# InexpensiveTNC-v4-mod.net
KiCad netlist of a schematic drawn in EAGLE
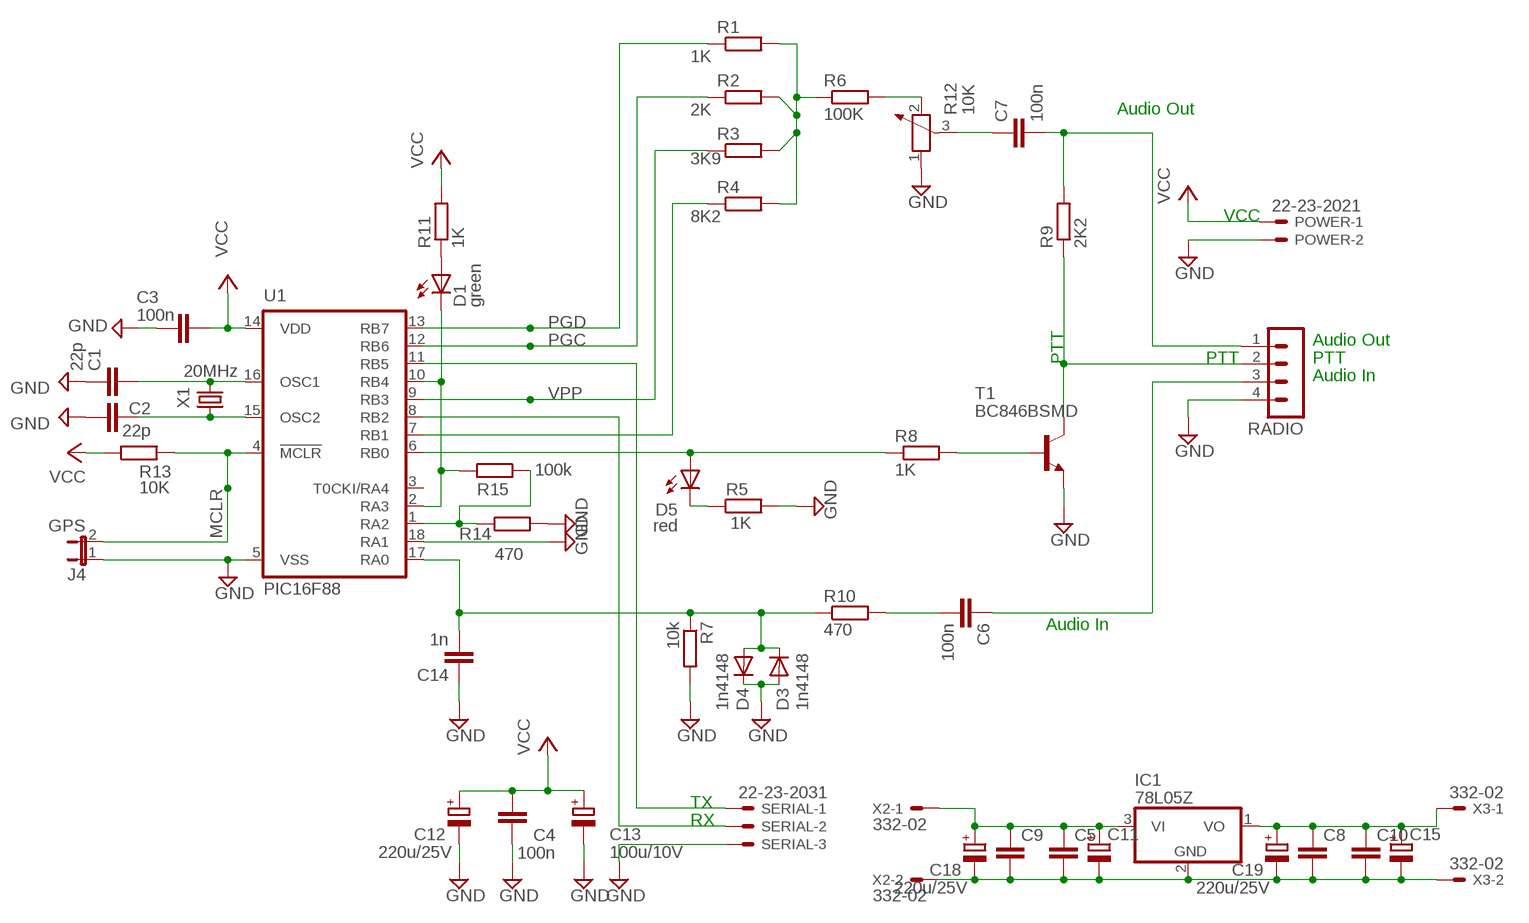
[diagram p0: schematic, sheet 1]

(export (version "E")
  (design (tool "Eeschema 10.0.6"))
  (components
    (comp (ref "C1")
      (value "22p")
      (footprint "eagle-import:C0805")
      (libsource (lib "eagle-import") (part "C-EUC0805"))
    )
    (comp (ref "C2")
      (value "22p")
      (footprint "eagle-import:C0805")
      (libsource (lib "eagle-import") (part "C-EUC0805"))
    )
    (comp (ref "C3")
      (value "100n")
      (footprint "eagle-import:C0805")
      (libsource (lib "eagle-import") (part "C-EUC0805"))
    )
    (comp (ref "C4")
      (value "100n")
      (footprint "eagle-import:C0805")
      (libsource (lib "eagle-import") (part "C-EUC0805"))
    )
    (comp (ref "C5")
      (value "C-EU025-025X050")
      (footprint "eagle-import:C025-025X050")
      (libsource (lib "eagle-import") (part "C-EU025-025X050"))
    )
    (comp (ref "C6")
      (value "100n")
      (footprint "eagle-import:C0805")
      (libsource (lib "eagle-import") (part "C-EUC0805"))
    )
    (comp (ref "C7")
      (value "100n")
      (footprint "eagle-import:C0805")
      (libsource (lib "eagle-import") (part "C-EUC0805"))
    )
    (comp (ref "C8")
      (value "C-EU025-025X050")
      (footprint "eagle-import:C025-025X050")
      (libsource (lib "eagle-import") (part "C-EU025-025X050"))
    )
    (comp (ref "C9")
      (value "C-EUC0805K")
      (footprint "eagle-import:C0805K")
      (libsource (lib "eagle-import") (part "C-EUC0805K"))
    )
    (comp (ref "C10")
      (value "C-EUC0805K")
      (footprint "eagle-import:C0805K")
      (libsource (lib "eagle-import") (part "C-EUC0805K"))
    )
    (comp (ref "C11")
      (value "CPOL-EUE3.5-10")
      (footprint "eagle-import:E3,5-10")
      (libsource (lib "eagle-import") (part "CPOL-EUE3.5-10"))
    )
    (comp (ref "C12")
      (value "220u/25V")
      (footprint "eagle-import:PANASONIC_A")
      (libsource (lib "eagle-import") (part "CPOL-EUA"))
    )
    (comp (ref "C13")
      (value "100u/10V")
      (footprint "eagle-import:PANASONIC_A")
      (libsource (lib "eagle-import") (part "CPOL-EUA"))
    )
    (comp (ref "C14")
      (value "1n")
      (footprint "eagle-import:C0805")
      (libsource (lib "eagle-import") (part "C-EUC0805"))
    )
    (comp (ref "C15")
      (value "CPOL-EUE3.5-10")
      (footprint "eagle-import:E3,5-10")
      (libsource (lib "eagle-import") (part "CPOL-EUE3.5-10"))
    )
    (comp (ref "C18")
      (value "220u/25V")
      (footprint "eagle-import:PANASONIC_A")
      (libsource (lib "eagle-import") (part "CPOL-EUA"))
    )
    (comp (ref "C19")
      (value "220u/25V")
      (footprint "eagle-import:PANASONIC_A")
      (libsource (lib "eagle-import") (part "CPOL-EUA"))
    )
    (comp (ref "D1")
      (value "green")
      (footprint "eagle-import:CHIPLED_1206")
      (libsource (lib "eagle-import") (part "LEDCHIPLED_1206"))
    )
    (comp (ref "D3")
      (value "1n4148")
      (footprint "eagle-import:MINIMELF")
      (libsource (lib "eagle-import") (part "DIODE-MINIMELF"))
    )
    (comp (ref "D4")
      (value "1n4148")
      (footprint "eagle-import:MINIMELF")
      (libsource (lib "eagle-import") (part "DIODE-MINIMELF"))
    )
    (comp (ref "D5")
      (value "red")
      (footprint "eagle-import:CHIPLED_1206")
      (libsource (lib "eagle-import") (part "LEDCHIPLED_1206"))
    )
    (comp (ref "IC1")
      (value "78L05Z")
      (footprint "eagle-import:TO92")
      (libsource (lib "eagle-import") (part "78ZL05"))
    )
    (comp (ref "J4")
      (value "GPS")
      (footprint "eagle-import:JP1")
      (libsource (lib "eagle-import") (part "JP1E"))
    )
    (comp (ref "POWER")
      (value "22-23-2021")
      (footprint "eagle-import:22-23-2021")
      (fields (field (name "MF") "MOLEX"))
      (libsource (lib "eagle-import") (part "22-23-2021"))
    )
    (comp (ref "R1")
      (value "1K")
      (footprint "eagle-import:R0805W")
      (libsource (lib "eagle-import") (part "R-EU_R0805W"))
    )
    (comp (ref "R2")
      (value "2K")
      (footprint "eagle-import:R0805W")
      (libsource (lib "eagle-import") (part "R-EU_R0805W"))
    )
    (comp (ref "R3")
      (value "3K9")
      (footprint "eagle-import:R0805W")
      (libsource (lib "eagle-import") (part "R-EU_R0805W"))
    )
    (comp (ref "R4")
      (value "8K2")
      (footprint "eagle-import:R0805W")
      (libsource (lib "eagle-import") (part "R-EU_R0805W"))
    )
    (comp (ref "R5")
      (value "1K")
      (footprint "eagle-import:R0805W")
      (libsource (lib "eagle-import") (part "R-EU_R0805W"))
    )
    (comp (ref "R6")
      (value "100K")
      (footprint "eagle-import:R0805W")
      (libsource (lib "eagle-import") (part "R-EU_R0805W"))
    )
    (comp (ref "R7")
      (value "10k")
      (footprint "eagle-import:R0805W")
      (libsource (lib "eagle-import") (part "R-EU_R0805W"))
    )
    (comp (ref "R8")
      (value "1K")
      (footprint "eagle-import:R0805W")
      (libsource (lib "eagle-import") (part "R-EU_R0805W"))
    )
    (comp (ref "R9")
      (value "2K2")
      (footprint "eagle-import:R0805W")
      (libsource (lib "eagle-import") (part "R-EU_R0805W"))
    )
    (comp (ref "R10")
      (value "470")
      (footprint "eagle-import:R0805W")
      (libsource (lib "eagle-import") (part "R-EU_R0805W"))
    )
    (comp (ref "R11")
      (value "1K")
      (footprint "eagle-import:R0805W")
      (libsource (lib "eagle-import") (part "R-EU_R0805W"))
    )
    (comp (ref "R12")
      (value "10K")
      (footprint "eagle-import:PT-10S")
      (libsource (lib "eagle-import") (part "POTENTIOMETER_PT-10S"))
    )
    (comp (ref "R13")
      (value "10K")
      (footprint "eagle-import:R0805W")
      (libsource (lib "eagle-import") (part "R-EU_R0805W"))
    )
    (comp (ref "R14")
      (value "470")
      (footprint "eagle-import:R0805W")
      (libsource (lib "eagle-import") (part "R-EU_R0805W"))
    )
    (comp (ref "R15")
      (value "100k")
      (footprint "eagle-import:R0805W")
      (libsource (lib "eagle-import") (part "R-EU_R0805W"))
    )
    (comp (ref "RADIO")
      (value "MA04-1")
      (footprint "eagle-import:MA04-1")
      (libsource (lib "eagle-import") (part "MA04-1"))
    )
    (comp (ref "SERIAL")
      (value "22-23-2031")
      (footprint "eagle-import:22-23-2031")
      (fields (field (name "MF") "MOLEX"))
      (libsource (lib "eagle-import") (part "22-23-2031"))
    )
    (comp (ref "T1")
      (value "BC846BSMD")
      (footprint "eagle-import:SOT23")
      (libsource (lib "eagle-import") (part "BC846SMDB"))
    )
    (comp (ref "U1")
      (value "PIC16F88")
      (footprint "eagle-import:SO-18W")
      (fields
        (field (name "MF") "MICROCHIP")
        (field (name "MPN") "PIC16F83-04/SO")
        (field (name "MPN_1") "PIC16F83-04/SO")
        (field (name "OC_FARNELL") "unknown")
        (field (name "OC_NEWARK") "23C4997")
      )
      (libsource (lib "eagle-import") (part "PIC16F8SO3"))
    )
    (comp (ref "X1")
      (value "20MHz")
      (footprint "eagle-import:HC49U70")
      (libsource (lib "eagle-import") (part "CRYSTALHC49U70"))
    )
    (comp (ref "X2")
      (value "332-02")
      (footprint "eagle-import:332-02")
      (libsource (lib "eagle-import") (part "332-02"))
    )
    (comp (ref "X3")
      (value "332-02")
      (footprint "eagle-import:332-02")
      (libsource (lib "eagle-import") (part "332-02"))
    )
  )
  (nets
    (net (code "1") (name "/MCLR") (class "Default")
      (node (ref "J4") (pin "2") (pinfunction "2_2") (pintype "passive"))
      (node (ref "R13") (pin "2") (pinfunction "2_2") (pintype "passive"))
      (node (ref "U1") (pin "4") (pinfunction "~{MCLR}_4") (pintype "input"))
    )
    (net (code "2") (name "/PGC") (class "Default")
      (node (ref "R2") (pin "1") (pinfunction "1_1") (pintype "passive"))
      (node (ref "U1") (pin "12") (pinfunction "RB6_12") (pintype "bidirectional"))
    )
    (net (code "3") (name "/PGD") (class "Default")
      (node (ref "R1") (pin "1") (pinfunction "1_1") (pintype "passive"))
      (node (ref "U1") (pin "13") (pinfunction "RB7_13") (pintype "bidirectional"))
    )
    (net (code "4") (name "/VPP") (class "Default")
      (node (ref "R3") (pin "1") (pinfunction "1_1") (pintype "passive"))
      (node (ref "U1") (pin "9") (pinfunction "RB3_9") (pintype "bidirectional"))
    )
    (net (code "5") (name "GND") (class "Default")
      (node (ref "C1") (pin "1") (pinfunction "1_1") (pintype "passive"))
      (node (ref "C12") (pin "-") (pinfunction "-_-") (pintype "passive"))
      (node (ref "C13") (pin "-") (pinfunction "-_-") (pintype "passive"))
      (node (ref "C14") (pin "1") (pinfunction "1_1") (pintype "passive"))
      (node (ref "C2") (pin "1") (pinfunction "1_1") (pintype "passive"))
      (node (ref "C3") (pin "2") (pinfunction "2_2") (pintype "passive"))
      (node (ref "C4") (pin "1") (pinfunction "1_1") (pintype "passive"))
      (node (ref "D3") (pin "A") (pinfunction "A_A") (pintype "passive"))
      (node (ref "D4") (pin "C") (pinfunction "C_C") (pintype "passive"))
      (node (ref "J4") (pin "1") (pinfunction "1_1") (pintype "passive"))
      (node (ref "POWER") (pin "2") (pinfunction "S_2") (pintype "passive"))
      (node (ref "R12") (pin "1") (pinfunction "1_1") (pintype "passive"))
      (node (ref "R14") (pin "2") (pinfunction "2_2") (pintype "passive"))
      (node (ref "R5") (pin "2") (pinfunction "2_2") (pintype "passive"))
      (node (ref "R7") (pin "2") (pinfunction "2_2") (pintype "passive"))
      (node (ref "RADIO") (pin "4") (pinfunction "4_4") (pintype "passive"))
      (node (ref "SERIAL") (pin "3") (pinfunction "S_3") (pintype "passive"))
      (node (ref "T1") (pin "2") (pinfunction "E_2") (pintype "passive"))
      (node (ref "U1") (pin "18") (pinfunction "RA1_18") (pintype "bidirectional"))
      (node (ref "U1") (pin "5") (pinfunction "VSS_5") (pintype "power_in"))
    )
    (net (code "6") (name "Net-(C6-Pad1)") (class "Default")
      (node (ref "C6") (pin "1") (pinfunction "1_1") (pintype "passive"))
      (node (ref "RADIO") (pin "3") (pinfunction "3_3") (pintype "passive"))
    )
    (net (code "7") (name "Net-(C6-Pad2)") (class "Default")
      (node (ref "C6") (pin "2") (pinfunction "2_2") (pintype "passive"))
      (node (ref "R10") (pin "2") (pinfunction "2_2") (pintype "passive"))
    )
    (net (code "8") (name "Net-(C7-Pad1)") (class "Default")
      (node (ref "C7") (pin "1") (pinfunction "1_1") (pintype "passive"))
      (node (ref "R12") (pin "3") (pinfunction "3_3") (pintype "passive"))
    )
    (net (code "9") (name "Net-(C7-Pad2)") (class "Default")
      (node (ref "C7") (pin "2") (pinfunction "2_2") (pintype "passive"))
      (node (ref "R9") (pin "2") (pinfunction "2_2") (pintype "passive"))
      (node (ref "RADIO") (pin "1") (pinfunction "1_1") (pintype "passive"))
    )
    (net (code "10") (name "Net-(D1-PadA)") (class "Default")
      (node (ref "D1") (pin "A") (pinfunction "A_A") (pintype "passive"))
      (node (ref "R11") (pin "1") (pinfunction "1_1") (pintype "passive"))
    )
    (net (code "11") (name "Net-(D5-PadC)") (class "Default")
      (node (ref "D5") (pin "C") (pinfunction "C_C") (pintype "passive"))
      (node (ref "R5") (pin "1") (pinfunction "1_1") (pintype "passive"))
    )
    (net (code "12") (name "Net-(IC1-GND)") (class "Default")
      (node (ref "C10") (pin "2") (pinfunction "2_2") (pintype "passive"))
      (node (ref "C11") (pin "-") (pinfunction "-_-") (pintype "passive"))
      (node (ref "C15") (pin "-") (pinfunction "-_-") (pintype "passive"))
      (node (ref "C18") (pin "-") (pinfunction "-_-") (pintype "passive"))
      (node (ref "C19") (pin "-") (pinfunction "-_-") (pintype "passive"))
      (node (ref "C5") (pin "2") (pinfunction "2_2") (pintype "passive"))
      (node (ref "C8") (pin "2") (pinfunction "2_2") (pintype "passive"))
      (node (ref "C9") (pin "2") (pinfunction "2_2") (pintype "passive"))
      (node (ref "IC1") (pin "2") (pinfunction "GND_2") (pintype "passive"))
      (node (ref "X2") (pin "2") (pinfunction "S_2") (pintype "passive"))
      (node (ref "X3") (pin "2") (pinfunction "S_2") (pintype "passive"))
    )
    (net (code "13") (name "Net-(IC1-VI)") (class "Default")
      (node (ref "C11") (pin "+") (pinfunction "+_+") (pintype "passive"))
      (node (ref "C18") (pin "+") (pinfunction "+_+") (pintype "passive"))
      (node (ref "C5") (pin "1") (pinfunction "1_1") (pintype "passive"))
      (node (ref "C9") (pin "1") (pinfunction "1_1") (pintype "passive"))
      (node (ref "IC1") (pin "3") (pinfunction "VI_3") (pintype "input"))
      (node (ref "X2") (pin "1") (pinfunction "S_1") (pintype "passive"))
    )
    (net (code "14") (name "Net-(IC1-VO)") (class "Default")
      (node (ref "C10") (pin "1") (pinfunction "1_1") (pintype "passive"))
      (node (ref "C15") (pin "+") (pinfunction "+_+") (pintype "passive"))
      (node (ref "C19") (pin "+") (pinfunction "+_+") (pintype "passive"))
      (node (ref "C8") (pin "1") (pinfunction "1_1") (pintype "passive"))
      (node (ref "IC1") (pin "1") (pinfunction "VO_1") (pintype "passive"))
      (node (ref "X3") (pin "1") (pinfunction "S_1") (pintype "passive"))
    )
    (net (code "15") (name "Net-(R1-Pad2)") (class "Default")
      (node (ref "R1") (pin "2") (pinfunction "2_2") (pintype "passive"))
      (node (ref "R2") (pin "2") (pinfunction "2_2") (pintype "passive"))
      (node (ref "R3") (pin "2") (pinfunction "2_2") (pintype "passive"))
      (node (ref "R4") (pin "2") (pinfunction "2_2") (pintype "passive"))
      (node (ref "R6") (pin "1") (pinfunction "1_1") (pintype "passive"))
    )
    (net (code "16") (name "Net-(R12-Pad2)") (class "Default")
      (node (ref "R12") (pin "2") (pinfunction "2_2") (pintype "passive"))
      (node (ref "R6") (pin "2") (pinfunction "2_2") (pintype "passive"))
    )
    (net (code "17") (name "Net-(SERIALA-S)") (class "Default")
      (node (ref "SERIAL") (pin "1") (pinfunction "S_1") (pintype "passive"))
      (node (ref "U1") (pin "11") (pinfunction "RB5_11") (pintype "bidirectional"))
    )
    (net (code "18") (name "Net-(SERIALB-S)") (class "Default")
      (node (ref "SERIAL") (pin "2") (pinfunction "S_2") (pintype "passive"))
      (node (ref "U1") (pin "8") (pinfunction "RB2_8") (pintype "bidirectional"))
    )
    (net (code "19") (name "Net-(T1-B)") (class "Default")
      (node (ref "R8") (pin "2") (pinfunction "2_2") (pintype "passive"))
      (node (ref "T1") (pin "1") (pinfunction "B_1") (pintype "passive"))
    )
    (net (code "20") (name "Net-(T1-C)") (class "Default")
      (node (ref "R9") (pin "1") (pinfunction "1_1") (pintype "passive"))
      (node (ref "RADIO") (pin "2") (pinfunction "2_2") (pintype "passive"))
      (node (ref "T1") (pin "3") (pinfunction "C_3") (pintype "passive"))
    )
    (net (code "21") (name "Net-(U1-OSC1)") (class "Default")
      (node (ref "C1") (pin "2") (pinfunction "2_2") (pintype "passive"))
      (node (ref "U1") (pin "16") (pinfunction "OSC1_16") (pintype "input"))
      (node (ref "X1") (pin "2") (pinfunction "2_2") (pintype "passive"))
    )
    (net (code "22") (name "Net-(U1-OSC2)") (class "Default")
      (node (ref "C2") (pin "2") (pinfunction "2_2") (pintype "passive"))
      (node (ref "U1") (pin "15") (pinfunction "OSC2_15") (pintype "output"))
      (node (ref "X1") (pin "1") (pinfunction "1_1") (pintype "passive"))
    )
    (net (code "23") (name "Net-(U1-RA0)") (class "Default")
      (node (ref "C14") (pin "2") (pinfunction "2_2") (pintype "passive"))
      (node (ref "D3") (pin "C") (pinfunction "C_C") (pintype "passive"))
      (node (ref "D4") (pin "A") (pinfunction "A_A") (pintype "passive"))
      (node (ref "R10") (pin "1") (pinfunction "1_1") (pintype "passive"))
      (node (ref "R7") (pin "1") (pinfunction "1_1") (pintype "passive"))
      (node (ref "U1") (pin "17") (pinfunction "RA0_17") (pintype "bidirectional"))
    )
    (net (code "24") (name "Net-(U1-RA2)") (class "Default")
      (node (ref "R14") (pin "1") (pinfunction "1_1") (pintype "passive"))
      (node (ref "R15") (pin "1") (pinfunction "1_1") (pintype "passive"))
      (node (ref "U1") (pin "1") (pinfunction "RA2_1") (pintype "bidirectional"))
    )
    (net (code "25") (name "Net-(U1-RA3)") (class "Default")
      (node (ref "D1") (pin "C") (pinfunction "C_C") (pintype "passive"))
      (node (ref "R15") (pin "2") (pinfunction "2_2") (pintype "passive"))
      (node (ref "U1") (pin "10") (pinfunction "RB4_10") (pintype "bidirectional"))
      (node (ref "U1") (pin "2") (pinfunction "RA3_2") (pintype "bidirectional"))
    )
    (net (code "26") (name "Net-(U1-RB0)") (class "Default")
      (node (ref "D5") (pin "A") (pinfunction "A_A") (pintype "passive"))
      (node (ref "R8") (pin "1") (pinfunction "1_1") (pintype "passive"))
      (node (ref "U1") (pin "6") (pinfunction "RB0_6") (pintype "bidirectional"))
    )
    (net (code "27") (name "Net-(U1-RB1)") (class "Default")
      (node (ref "R4") (pin "1") (pinfunction "1_1") (pintype "passive"))
      (node (ref "U1") (pin "7") (pinfunction "RB1_7") (pintype "bidirectional"))
    )
    (net (code "28") (name "VCC") (class "Default")
      (node (ref "C12") (pin "+") (pinfunction "+_+") (pintype "passive"))
      (node (ref "C13") (pin "+") (pinfunction "+_+") (pintype "passive"))
      (node (ref "C3") (pin "1") (pinfunction "1_1") (pintype "passive"))
      (node (ref "C4") (pin "2") (pinfunction "2_2") (pintype "passive"))
      (node (ref "POWER") (pin "1") (pinfunction "S_1") (pintype "passive"))
      (node (ref "R11") (pin "2") (pinfunction "2_2") (pintype "passive"))
      (node (ref "R13") (pin "1") (pinfunction "1_1") (pintype "passive"))
      (node (ref "U1") (pin "14") (pinfunction "VDD_14") (pintype "power_in"))
    )
    (net (code "29") (name "unconnected-(U1-T0CKI{slash}RA4-Pad3)") (class "Default")
      (node (ref "U1") (pin "3") (pinfunction "T0CKI/RA4_3") (pintype "bidirectional"))
    )
  )
)
